# ir-sensor-breakout-mk-3_0-smd.net
KiCad netlist of a schematic drawn in EAGLE
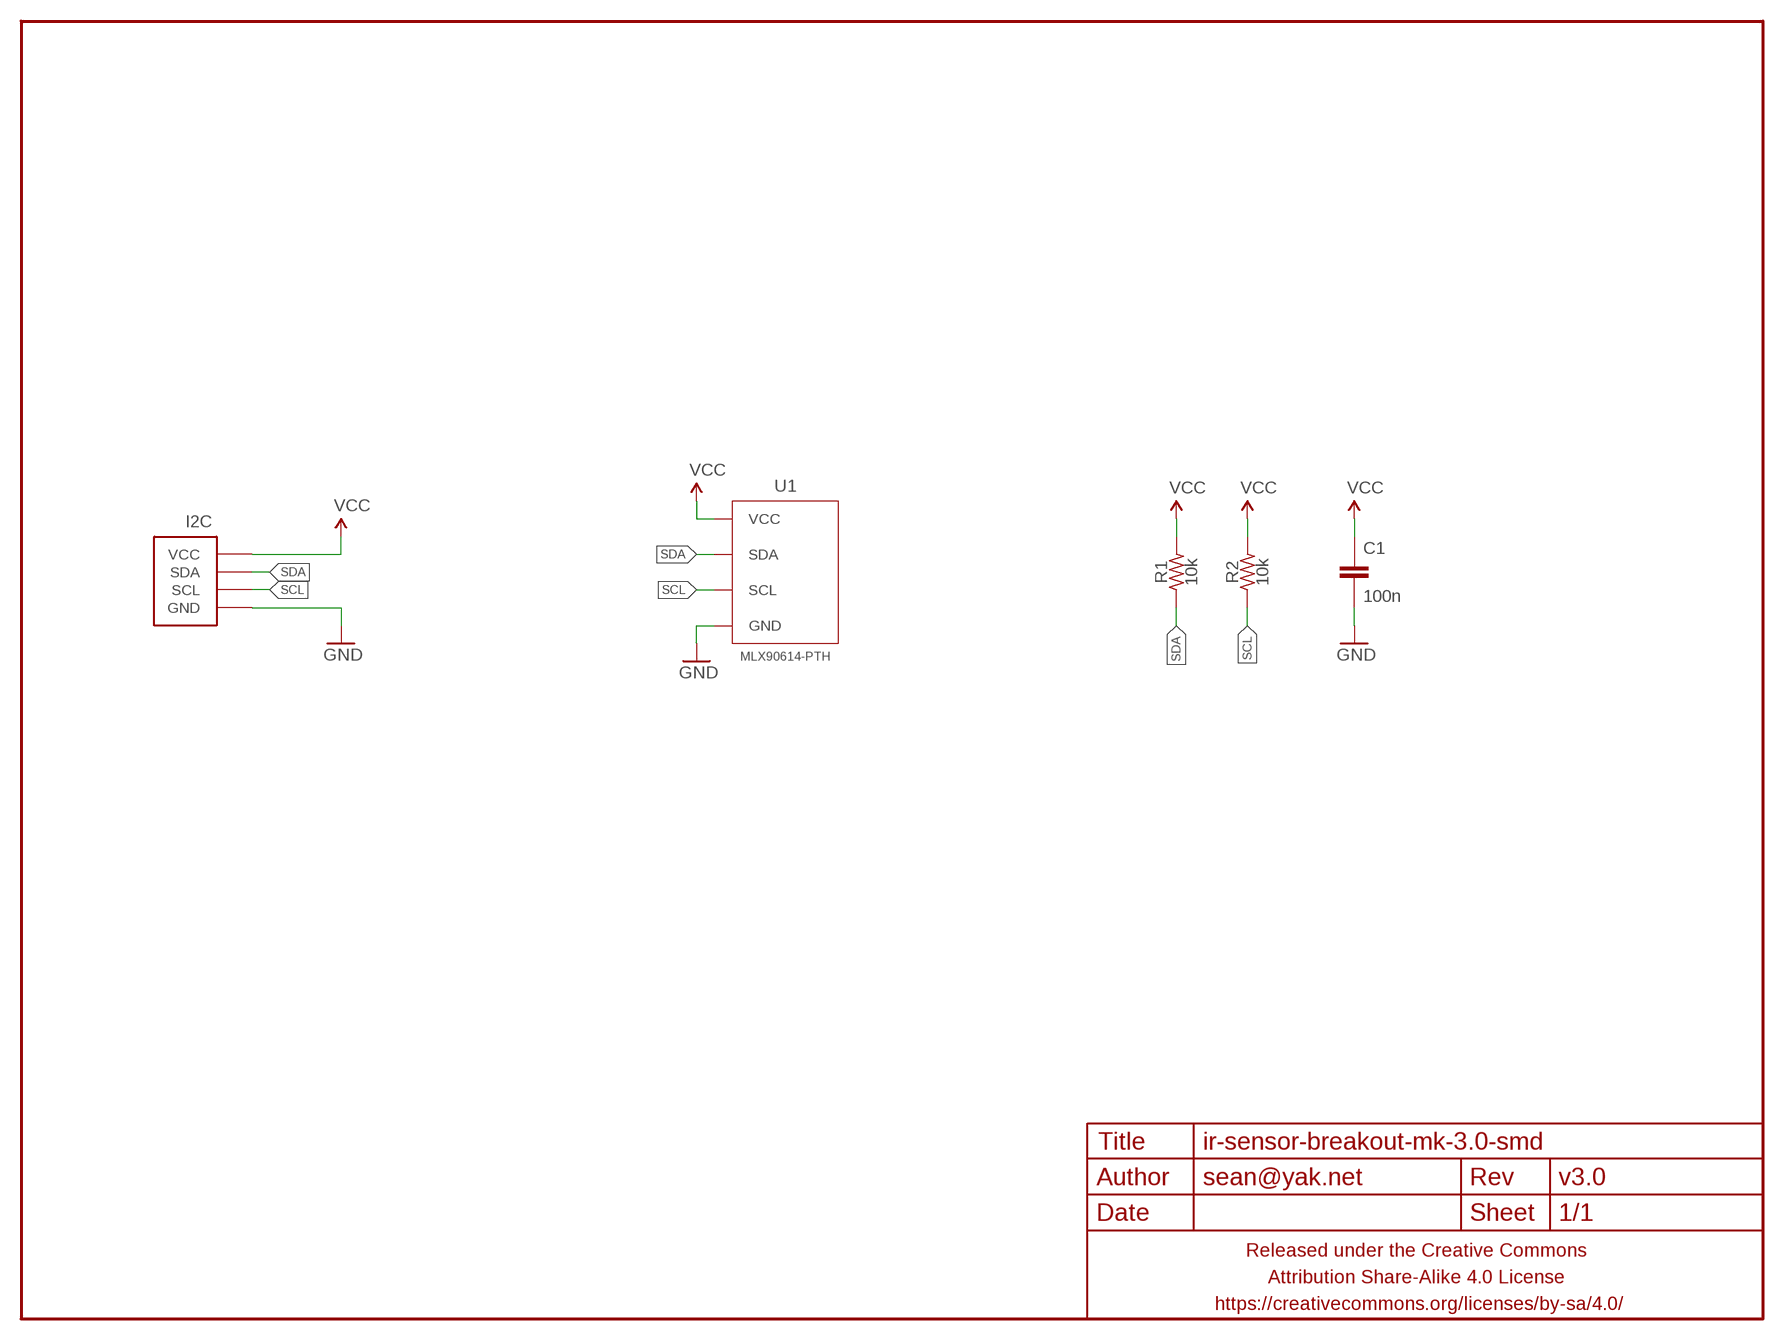
[diagram p0: schematic, sheet 1]

(export (version "E")
  (design (tool "Eeschema 10.0.6"))
  (components
    (comp (ref "C1")
      (value "100n")
      (footprint "eagle-import:C0805")
      (libsource (lib "eagle-import") (part "CAPACITOR-CERAMICC0805"))
    )
    (comp (ref "FRAME1")
      (value "FRAME-LETTERNO_PACKAGE")
      (footprint "eagle-import:DUMMY")
      (fields (field (name "DESIGNER") "sean@yak.net") (field (name "VERSION") "v3.0"))
      (libsource (lib "eagle-import") (part "FRAME-LETTERNO_PACKAGE"))
    )
    (comp (ref "I2C")
      (value "M04-I2CPTH-0.1IN-CENTERED-FLIPPED")
      (footprint "eagle-import:1X04-PTH-VERT-I2C-CENTERED-FLIPPED")
      (libsource (lib "eagle-import") (part "M04-I2CPTH-0.1IN-CENTERED-FLIPPED"))
    )
    (comp (ref "R1")
      (value "10k")
      (footprint "eagle-import:R0805")
      (libsource (lib "eagle-import") (part "RESISTORR0805"))
    )
    (comp (ref "R2")
      (value "10k")
      (footprint "eagle-import:R0805")
      (libsource (lib "eagle-import") (part "RESISTORR0805"))
    )
    (comp (ref "U1")
      (value "MLX90614-PTH")
      (footprint "eagle-import:TO-39-4")
      (libsource (lib "eagle-import") (part "MLX906145V-PTH"))
    )
  )
  (nets
    (net (code "1") (name "GND") (class "Default")
      (node (ref "C1") (pin "2") (pinfunction "2_2") (pintype "passive"))
      (node (ref "I2C") (pin "GND") (pinfunction "GND_GND") (pintype "bidirectional"))
      (node (ref "U1") (pin "4") (pinfunction "GND_4") (pintype "bidirectional"))
    )
    (net (code "2") (name "SCL") (class "Default")
      (node (ref "I2C") (pin "SCL") (pinfunction "SCL_SCL") (pintype "bidirectional"))
      (node (ref "R2") (pin "1") (pinfunction "1_1") (pintype "passive"))
      (node (ref "U1") (pin "1") (pinfunction "SCL_1") (pintype "bidirectional"))
    )
    (net (code "3") (name "SDA") (class "Default")
      (node (ref "I2C") (pin "SDA") (pinfunction "SDA_SDA") (pintype "bidirectional"))
      (node (ref "R1") (pin "1") (pinfunction "1_1") (pintype "passive"))
      (node (ref "U1") (pin "2") (pinfunction "SDA_2") (pintype "bidirectional"))
    )
    (net (code "4") (name "VCC") (class "Default")
      (node (ref "C1") (pin "1") (pinfunction "1_1") (pintype "passive"))
      (node (ref "I2C") (pin "VCC") (pinfunction "VCC_VCC") (pintype "bidirectional"))
      (node (ref "R1") (pin "2") (pinfunction "2_2") (pintype "passive"))
      (node (ref "R2") (pin "2") (pinfunction "2_2") (pintype "passive"))
      (node (ref "U1") (pin "3") (pinfunction "VCC_3") (pintype "bidirectional"))
    )
  )
)
